# DAC_AFE_Mezzanine.net
KiCad netlist of a schematic drawn in Altium Designer
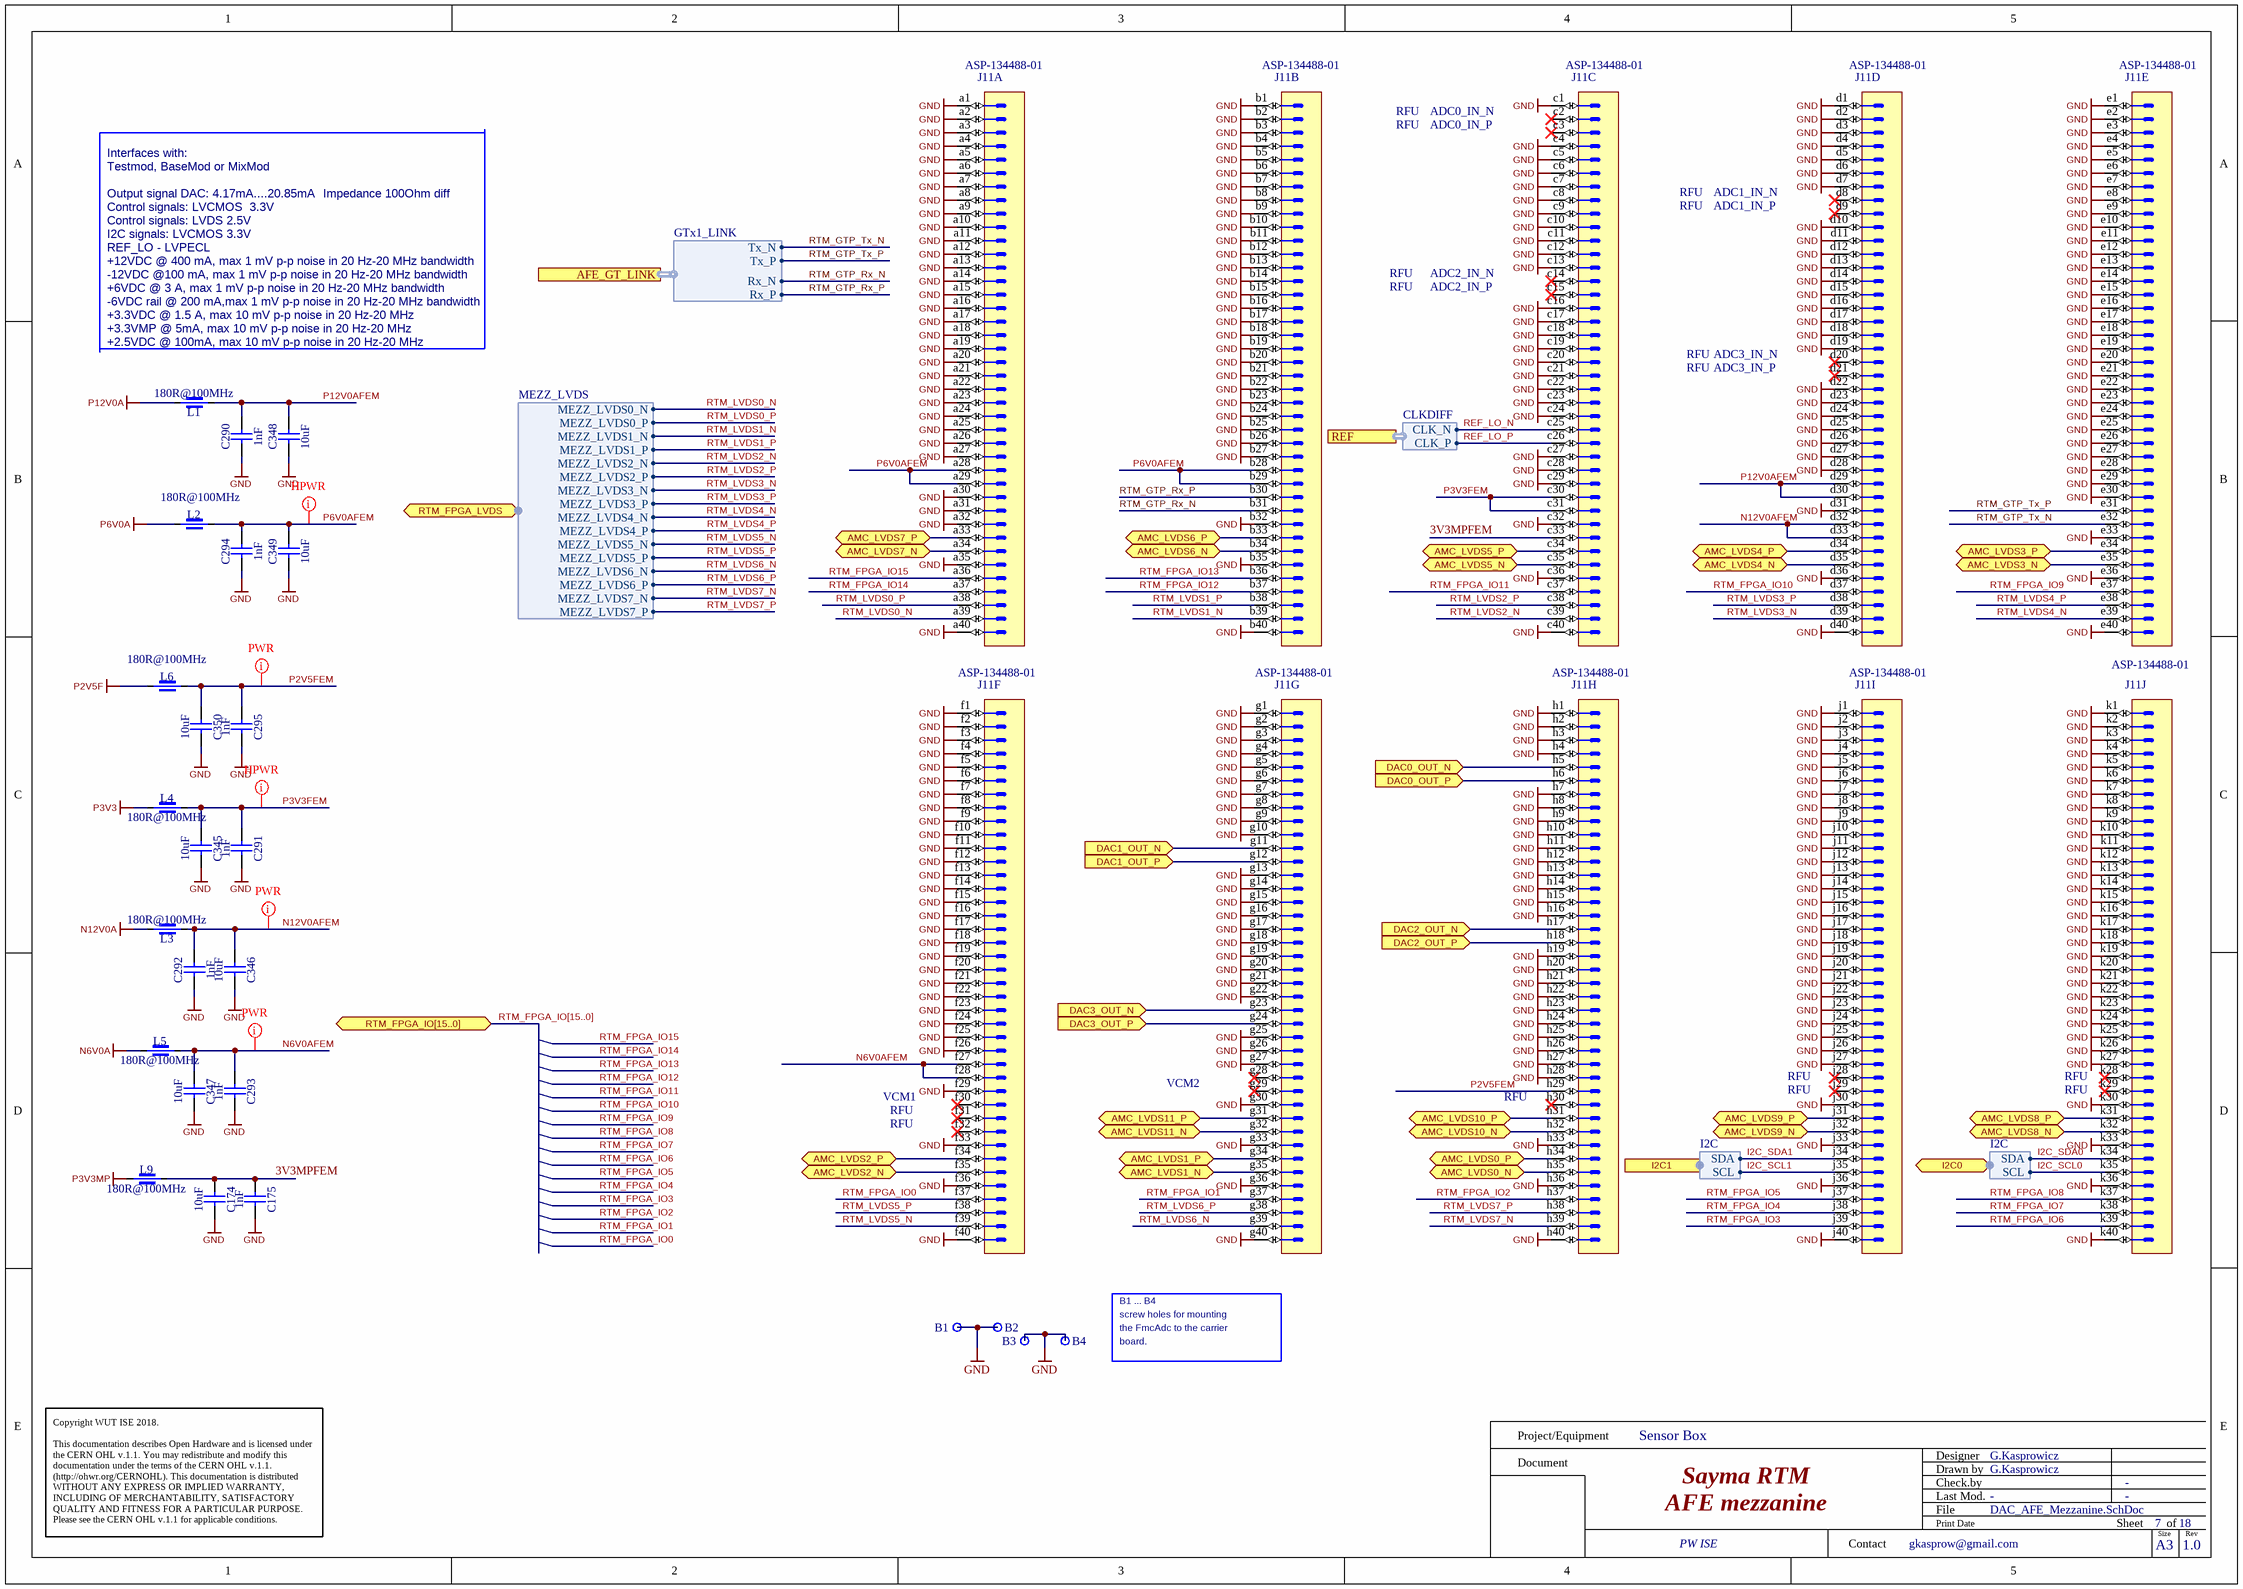
[diagram p0: DAC_AFE_Mezzanine.SchDoc]

(export (version "E")
  (design (tool "Eeschema 10.0.6"))
  (components
    (comp (ref "B1")
      (value "Plated Hole")
      (footprint "MTG270_500")
      (description "Single Terminal Socket")
      (fields (field (name "PART NUMBER") "PLATED_HOLE2.7_PAD5.0") (field (name "AUTHOR") "CERN DEM JMW"))
      (libsource (lib "Eletro-mechanical") (part "Single Terminal Socket"))
    )
    (comp (ref "B2")
      (value "Plated Hole")
      (footprint "MTG270_500")
      (description "Single Terminal Socket")
      (fields (field (name "PART NUMBER") "PLATED_HOLE2.7_PAD5.0") (field (name "AUTHOR") "CERN DEM JMW"))
      (libsource (lib "Eletro-mechanical") (part "Single Terminal Socket"))
    )
    (comp (ref "B3")
      (value "Plated Hole")
      (footprint "MTG270_500")
      (description "Single Terminal Socket")
      (fields (field (name "PART NUMBER") "PLATED_HOLE2.7_PAD5.0") (field (name "AUTHOR") "CERN DEM JMW"))
      (libsource (lib "Eletro-mechanical") (part "Single Terminal Socket"))
    )
    (comp (ref "B4")
      (value "Plated Hole")
      (footprint "MTG270_500")
      (description "Single Terminal Socket")
      (fields (field (name "PART NUMBER") "PLATED_HOLE2.7_PAD5.0") (field (name "AUTHOR") "CERN DEM JMW"))
      (libsource (lib "Eletro-mechanical") (part "Single Terminal Socket"))
    )
    (comp (ref "C174")
      (value "10uF")
      (footprint "CAPC3216X180N")
      (description "Non-polarised capacitor")
      (fields
        (field (name "MANUFACTURER PART NUMBER") "CC1206_10uF_25V_10%_X7R")
        (field (name "MANUFACTURER") "GENERIC")
        (field (name "AUTHOR") "CERN DEM JLC")
      )
      (libsource (lib "Capacitors") (part "Capacitor - non polarized"))
    )
    (comp (ref "C175")
      (value "1nF")
      (footprint "CAPC1608X90N")
      (description "Non-polarised capacitor")
      (fields
        (field (name "MANUFACTURER PART NUMBER") "CC0603_1NF_50V_5%_NP0")
        (field (name "MANUFACTURER") "GENERIC")
        (field (name "AUTHOR") "CERN DEM JLC")
      )
      (libsource (lib "Capacitors") (part "Capacitor - non polarized"))
    )
    (comp (ref "C290")
      (value "1nF")
      (footprint "CAPC1608X90N")
      (description "Non-polarised capacitor")
      (fields
        (field (name "MANUFACTURER PART NUMBER") "CC0603_1NF_50V_5%_NP0")
        (field (name "MANUFACTURER") "GENERIC")
        (field (name "AUTHOR") "CERN DEM JLC")
      )
      (libsource (lib "Capacitors") (part "Capacitor - non polarized"))
    )
    (comp (ref "C291")
      (value "1nF")
      (footprint "CAPC1608X90N")
      (description "Non-polarised capacitor")
      (fields
        (field (name "MANUFACTURER PART NUMBER") "CC0603_1NF_50V_5%_NP0")
        (field (name "MANUFACTURER") "GENERIC")
        (field (name "AUTHOR") "CERN DEM JLC")
      )
      (libsource (lib "Capacitors") (part "Capacitor - non polarized"))
    )
    (comp (ref "C292")
      (value "1nF")
      (footprint "CAPC1608X90N")
      (description "Non-polarised capacitor")
      (fields
        (field (name "MANUFACTURER PART NUMBER") "CC0603_1NF_50V_5%_NP0")
        (field (name "MANUFACTURER") "GENERIC")
        (field (name "AUTHOR") "CERN DEM JLC")
      )
      (libsource (lib "Capacitors") (part "Capacitor - non polarized"))
    )
    (comp (ref "C293")
      (value "1nF")
      (footprint "CAPC1608X90N")
      (description "Non-polarised capacitor")
      (fields
        (field (name "MANUFACTURER PART NUMBER") "CC0603_1NF_50V_5%_NP0")
        (field (name "MANUFACTURER") "GENERIC")
        (field (name "AUTHOR") "CERN DEM JLC")
      )
      (libsource (lib "Capacitors") (part "Capacitor - non polarized"))
    )
    (comp (ref "C294")
      (value "1nF")
      (footprint "CAPC1608X90N")
      (description "Non-polarised capacitor")
      (fields
        (field (name "MANUFACTURER PART NUMBER") "CC0603_1NF_50V_5%_NP0")
        (field (name "MANUFACTURER") "GENERIC")
        (field (name "AUTHOR") "CERN DEM JLC")
      )
      (libsource (lib "Capacitors") (part "Capacitor - non polarized"))
    )
    (comp (ref "C295")
      (value "1nF")
      (footprint "CAPC1608X90N")
      (description "Non-polarised capacitor")
      (fields
        (field (name "MANUFACTURER PART NUMBER") "CC0603_1NF_50V_5%_NP0")
        (field (name "MANUFACTURER") "GENERIC")
        (field (name "AUTHOR") "CERN DEM JLC")
      )
      (libsource (lib "Capacitors") (part "Capacitor - non polarized"))
    )
    (comp (ref "C345")
      (value "10uF")
      (footprint "CAPC3216X180N")
      (description "Non-polarised capacitor")
      (fields
        (field (name "MANUFACTURER PART NUMBER") "CC1206_10uF_25V_10%_X7R")
        (field (name "MANUFACTURER") "GENERIC")
        (field (name "AUTHOR") "CERN DEM JLC")
      )
      (libsource (lib "Capacitors") (part "Capacitor - non polarized"))
    )
    (comp (ref "C346")
      (value "10uF")
      (footprint "CAPC3216X180N")
      (description "Non-polarised capacitor")
      (fields
        (field (name "MANUFACTURER PART NUMBER") "CC1206_10uF_25V_10%_X7R")
        (field (name "MANUFACTURER") "GENERIC")
        (field (name "AUTHOR") "CERN DEM JLC")
      )
      (libsource (lib "Capacitors") (part "Capacitor - non polarized"))
    )
    (comp (ref "C347")
      (value "10uF")
      (footprint "CAPC3216X180N")
      (description "Non-polarised capacitor")
      (fields
        (field (name "MANUFACTURER PART NUMBER") "CC1206_10uF_25V_10%_X7R")
        (field (name "MANUFACTURER") "GENERIC")
        (field (name "AUTHOR") "CERN DEM JLC")
      )
      (libsource (lib "Capacitors") (part "Capacitor - non polarized"))
    )
    (comp (ref "C348")
      (value "10uF")
      (footprint "CAPC3216X180N")
      (description "Non-polarised capacitor")
      (fields
        (field (name "MANUFACTURER PART NUMBER") "CC1206_10uF_25V_10%_X7R")
        (field (name "MANUFACTURER") "GENERIC")
        (field (name "AUTHOR") "CERN DEM JLC")
      )
      (libsource (lib "Capacitors") (part "Capacitor - non polarized"))
    )
    (comp (ref "C349")
      (value "10uF")
      (footprint "CAPC3216X180N")
      (description "Non-polarised capacitor")
      (fields
        (field (name "MANUFACTURER PART NUMBER") "CC1206_10uF_25V_10%_X7R")
        (field (name "MANUFACTURER") "GENERIC")
        (field (name "AUTHOR") "CERN DEM JLC")
      )
      (libsource (lib "Capacitors") (part "Capacitor - non polarized"))
    )
    (comp (ref "C350")
      (value "10uF")
      (footprint "CAPC3216X180N")
      (description "Non-polarised capacitor")
      (fields
        (field (name "MANUFACTURER PART NUMBER") "CC1206_10uF_25V_10%_X7R")
        (field (name "MANUFACTURER") "GENERIC")
        (field (name "AUTHOR") "CERN DEM JLC")
      )
      (libsource (lib "Capacitors") (part "Capacitor - non polarized"))
    )
    (comp (ref "J11")
      (value "VITA 57")
      (footprint "SAMTEC_ASP-134488-01")
      (description "Connector VITA 57, 400 Male contacts in 10 row abcdefghj")
      (fields
        (field (name "MANUFACTURER PART NUMBER") "ASP-134488-01")
        (field (name "MANUFACTURER") "SAMTEC")
        (field (name "PART NUMBER") "SAMTEC_ASP-134488-01")
        (field (name "AUTHOR") "CERN DEM JLC")
      )
      (libsource (lib "Connectors") (part "Connector VITA 57 400 Male (abcdefghjk)"))
    )
    (comp (ref "L1")
      (value "180R@100MHz")
      (footprint "INDC4516X180N")
      (fields
        (field (name "MANUFACTURER PART NUMBER") "BLM41PG181SN1L")
        (field (name "MANUFACTURER") "MURATA")
        (field (name "PART NUMBER") "IND1806_MURATA_BLM41PG181SN1L")
        (field (name "AUTHOR") "CERN DEM JLC")
      )
      (libsource (lib "") (part "Ferrite Bead_3"))
    )
    (comp (ref "L2")
      (value "180R@100MHz")
      (footprint "INDC4516X180N")
      (fields
        (field (name "MANUFACTURER PART NUMBER") "BLM41PG181SN1L")
        (field (name "MANUFACTURER") "MURATA")
        (field (name "PART NUMBER") "IND1806_MURATA_BLM41PG181SN1L")
        (field (name "AUTHOR") "CERN DEM JLC")
      )
      (libsource (lib "") (part "Ferrite Bead_2"))
    )
    (comp (ref "L3")
      (value "180R@100MHz")
      (footprint "INDC4516X180N")
      (fields
        (field (name "MANUFACTURER PART NUMBER") "BLM41PG181SN1L")
        (field (name "MANUFACTURER") "MURATA")
        (field (name "PART NUMBER") "IND1806_MURATA_BLM41PG181SN1L")
        (field (name "AUTHOR") "CERN DEM JLC")
      )
      (libsource (lib "Inductors & Transformers") (part "Ferrite Bead"))
    )
    (comp (ref "L4")
      (value "180R@100MHz")
      (footprint "INDC4516X180N")
      (fields
        (field (name "MANUFACTURER PART NUMBER") "BLM41PG181SN1L")
        (field (name "MANUFACTURER") "MURATA")
        (field (name "PART NUMBER") "IND1806_MURATA_BLM41PG181SN1L")
        (field (name "AUTHOR") "CERN DEM JLC")
      )
      (libsource (lib "") (part "Ferrite Bead_1"))
    )
    (comp (ref "L5")
      (value "180R@100MHz")
      (footprint "INDC4516X180N")
      (fields
        (field (name "MANUFACTURER PART NUMBER") "BLM41PG181SN1L")
        (field (name "MANUFACTURER") "MURATA")
        (field (name "PART NUMBER") "IND1806_MURATA_BLM41PG181SN1L")
        (field (name "AUTHOR") "CERN DEM JLC")
      )
      (libsource (lib "") (part "Ferrite Bead_1"))
    )
    (comp (ref "L6")
      (value "180R@100MHz")
      (footprint "INDC4516X180N")
      (fields
        (field (name "MANUFACTURER PART NUMBER") "BLM41PG181SN1L")
        (field (name "MANUFACTURER") "MURATA")
        (field (name "PART NUMBER") "IND1806_MURATA_BLM41PG181SN1L")
        (field (name "AUTHOR") "CERN DEM JLC")
      )
      (libsource (lib "") (part "Ferrite Bead_1"))
    )
    (comp (ref "L9")
      (value "180R@100MHz")
      (footprint "INDC4516X180N")
      (fields
        (field (name "MANUFACTURER PART NUMBER") "BLM41PG181SN1L")
        (field (name "MANUFACTURER") "MURATA")
        (field (name "PART NUMBER") "IND1806_MURATA_BLM41PG181SN1L")
        (field (name "AUTHOR") "CERN DEM JLC")
      )
      (libsource (lib "") (part "Ferrite Bead_1"))
    )
  )
  (nets
    (net (code "5") (name "/3V3MPFEM") (class "Default")
      (node (ref "C174") (pin "2") (pinfunction "2_2") (pintype "passive"))
      (node (ref "C175") (pin "2") (pinfunction "2_2") (pintype "passive"))
      (node (ref "J11") (pin "c33") (pinfunction "c33_c33") (pintype "bidirectional"))
      (node (ref "L9") (pin "1") (pinfunction "1_1") (pintype "passive"))
    )
    (net (code "6") (name "/AMC_LVDS0_N") (class "Default")
      (node (ref "J11") (pin "h35") (pinfunction "h35_h35") (pintype "bidirectional"))
    )
    (net (code "7") (name "/AMC_LVDS0_P") (class "Default")
      (node (ref "J11") (pin "h34") (pinfunction "h34_h34") (pintype "bidirectional"))
    )
    (net (code "8") (name "/AMC_LVDS1_N") (class "Default")
      (node (ref "J11") (pin "g35") (pinfunction "g35_g35") (pintype "bidirectional"))
    )
    (net (code "9") (name "/AMC_LVDS1_P") (class "Default")
      (node (ref "J11") (pin "g34") (pinfunction "g34_g34") (pintype "bidirectional"))
    )
    (net (code "10") (name "/AMC_LVDS2_N") (class "Default")
      (node (ref "J11") (pin "f35") (pinfunction "f35_f35") (pintype "bidirectional"))
    )
    (net (code "11") (name "/AMC_LVDS2_P") (class "Default")
      (node (ref "J11") (pin "f34") (pinfunction "f34_f34") (pintype "bidirectional"))
    )
    (net (code "12") (name "/AMC_LVDS3_N") (class "Default")
      (node (ref "J11") (pin "e35") (pinfunction "e35_e35") (pintype "bidirectional"))
    )
    (net (code "13") (name "/AMC_LVDS3_P") (class "Default")
      (node (ref "J11") (pin "e34") (pinfunction "e34_e34") (pintype "bidirectional"))
    )
    (net (code "14") (name "/AMC_LVDS4_N") (class "Default")
      (node (ref "J11") (pin "d35") (pinfunction "d35_d35") (pintype "bidirectional"))
    )
    (net (code "15") (name "/AMC_LVDS4_P") (class "Default")
      (node (ref "J11") (pin "d34") (pinfunction "d34_d34") (pintype "bidirectional"))
    )
    (net (code "16") (name "/AMC_LVDS5_N") (class "Default")
      (node (ref "J11") (pin "c35") (pinfunction "c35_c35") (pintype "bidirectional"))
    )
    (net (code "17") (name "/AMC_LVDS5_P") (class "Default")
      (node (ref "J11") (pin "c34") (pinfunction "c34_c34") (pintype "bidirectional"))
    )
    (net (code "18") (name "/AMC_LVDS6_N") (class "Default")
      (node (ref "J11") (pin "b34") (pinfunction "b34_b34") (pintype "bidirectional"))
    )
    (net (code "19") (name "/AMC_LVDS6_P") (class "Default")
      (node (ref "J11") (pin "b33") (pinfunction "b33_b33") (pintype "bidirectional"))
    )
    (net (code "20") (name "/AMC_LVDS7_N") (class "Default")
      (node (ref "J11") (pin "a34") (pinfunction "a34_a34") (pintype "bidirectional"))
    )
    (net (code "21") (name "/AMC_LVDS7_P") (class "Default")
      (node (ref "J11") (pin "a33") (pinfunction "a33_a33") (pintype "bidirectional"))
    )
    (net (code "22") (name "/AMC_LVDS8_N") (class "Default")
      (node (ref "J11") (pin "k32") (pinfunction "k32_k32") (pintype "bidirectional"))
    )
    (net (code "23") (name "/AMC_LVDS8_P") (class "Default")
      (node (ref "J11") (pin "k31") (pinfunction "k31_k31") (pintype "bidirectional"))
    )
    (net (code "24") (name "/AMC_LVDS9_N") (class "Default")
      (node (ref "J11") (pin "j32") (pinfunction "j32_j32") (pintype "bidirectional"))
    )
    (net (code "25") (name "/AMC_LVDS9_P") (class "Default")
      (node (ref "J11") (pin "j31") (pinfunction "j31_j31") (pintype "bidirectional"))
    )
    (net (code "26") (name "/AMC_LVDS10_N") (class "Default")
      (node (ref "J11") (pin "h32") (pinfunction "h32_h32") (pintype "bidirectional"))
    )
    (net (code "27") (name "/AMC_LVDS10_P") (class "Default")
      (node (ref "J11") (pin "h31") (pinfunction "h31_h31") (pintype "bidirectional"))
    )
    (net (code "28") (name "/AMC_LVDS11_N") (class "Default")
      (node (ref "J11") (pin "g32") (pinfunction "g32_g32") (pintype "bidirectional"))
    )
    (net (code "29") (name "/AMC_LVDS11_P") (class "Default")
      (node (ref "J11") (pin "g31") (pinfunction "g31_g31") (pintype "bidirectional"))
    )
    (net (code "30") (name "/DAC0_OUT_N") (class "Default")
      (node (ref "J11") (pin "h5") (pinfunction "h5_h5") (pintype "bidirectional"))
    )
    (net (code "31") (name "/DAC0_OUT_P") (class "Default")
      (node (ref "J11") (pin "h6") (pinfunction "h6_h6") (pintype "bidirectional"))
    )
    (net (code "32") (name "/DAC1_OUT_N") (class "Default")
      (node (ref "J11") (pin "g11") (pinfunction "g11_g11") (pintype "bidirectional"))
    )
    (net (code "33") (name "/DAC1_OUT_P") (class "Default")
      (node (ref "J11") (pin "g12") (pinfunction "g12_g12") (pintype "bidirectional"))
    )
    (net (code "34") (name "/DAC2_OUT_N") (class "Default")
      (node (ref "J11") (pin "h17") (pinfunction "h17_h17") (pintype "bidirectional"))
    )
    (net (code "35") (name "/DAC2_OUT_P") (class "Default")
      (node (ref "J11") (pin "h18") (pinfunction "h18_h18") (pintype "bidirectional"))
    )
    (net (code "36") (name "/DAC3_OUT_N") (class "Default")
      (node (ref "J11") (pin "g23") (pinfunction "g23_g23") (pintype "bidirectional"))
    )
    (net (code "37") (name "/DAC3_OUT_P") (class "Default")
      (node (ref "J11") (pin "g24") (pinfunction "g24_g24") (pintype "bidirectional"))
    )
    (net (code "38") (name "/I2C_SCL0") (class "Default")
      (node (ref "J11") (pin "k35") (pinfunction "k35_k35") (pintype "bidirectional"))
    )
    (net (code "39") (name "/I2C_SCL1") (class "Default")
      (node (ref "J11") (pin "j35") (pinfunction "j35_j35") (pintype "bidirectional"))
    )
    (net (code "40") (name "/I2C_SDA0") (class "Default")
      (node (ref "J11") (pin "k34") (pinfunction "k34_k34") (pintype "bidirectional"))
    )
    (net (code "41") (name "/I2C_SDA1") (class "Default")
      (node (ref "J11") (pin "j34") (pinfunction "j34_j34") (pintype "bidirectional"))
    )
    (net (code "42") (name "/N6V0AFEM") (class "Default")
      (node (ref "C293") (pin "2") (pinfunction "2_2") (pintype "passive"))
      (node (ref "C347") (pin "2") (pinfunction "2_2") (pintype "passive"))
      (node (ref "J11") (pin "f27") (pinfunction "f27_f27") (pintype "bidirectional"))
      (node (ref "J11") (pin "f28") (pinfunction "f28_f28") (pintype "bidirectional"))
      (node (ref "L5") (pin "1") (pinfunction "1_1") (pintype "passive"))
    )
    (net (code "43") (name "/N12V0AFEM") (class "Default")
      (node (ref "C292") (pin "2") (pinfunction "2_2") (pintype "passive"))
      (node (ref "C346") (pin "1") (pinfunction "1_1") (pintype "passive"))
      (node (ref "J11") (pin "d32") (pinfunction "d32_d32") (pintype "bidirectional"))
      (node (ref "J11") (pin "d33") (pinfunction "d33_d33") (pintype "bidirectional"))
      (node (ref "L3") (pin "1") (pinfunction "1_1") (pintype "passive"))
    )
    (net (code "44") (name "/P2V5FEM") (class "Default")
      (node (ref "C295") (pin "2") (pinfunction "2_2") (pintype "passive"))
      (node (ref "C350") (pin "2") (pinfunction "2_2") (pintype "passive"))
      (node (ref "J11") (pin "h29") (pinfunction "h29_h29") (pintype "bidirectional"))
      (node (ref "L6") (pin "1") (pinfunction "1_1") (pintype "passive"))
    )
    (net (code "45") (name "/P3V3FEM") (class "Default")
      (node (ref "C291") (pin "2") (pinfunction "2_2") (pintype "passive"))
      (node (ref "C345") (pin "2") (pinfunction "2_2") (pintype "passive"))
      (node (ref "J11") (pin "c30") (pinfunction "c30_c30") (pintype "bidirectional"))
      (node (ref "J11") (pin "c31") (pinfunction "c31_c31") (pintype "bidirectional"))
      (node (ref "L4") (pin "1") (pinfunction "1_1") (pintype "passive"))
    )
    (net (code "46") (name "/P6V0AFEM") (class "Default")
      (node (ref "C294") (pin "2") (pinfunction "2_2") (pintype "passive"))
      (node (ref "C349") (pin "2") (pinfunction "2_2") (pintype "passive"))
      (node (ref "J11") (pin "a28") (pinfunction "a28_a28") (pintype "bidirectional"))
      (node (ref "J11") (pin "a29") (pinfunction "a29_a29") (pintype "bidirectional"))
      (node (ref "J11") (pin "b28") (pinfunction "b28_b28") (pintype "bidirectional"))
      (node (ref "J11") (pin "b29") (pinfunction "b29_b29") (pintype "bidirectional"))
      (node (ref "L2") (pin "2") (pinfunction "2_2") (pintype "passive"))
    )
    (net (code "47") (name "/P12V0AFEM") (class "Default")
      (node (ref "C290") (pin "1") (pinfunction "1_1") (pintype "passive"))
      (node (ref "C348") (pin "1") (pinfunction "1_1") (pintype "passive"))
      (node (ref "J11") (pin "d29") (pinfunction "d29_d29") (pintype "bidirectional"))
      (node (ref "J11") (pin "d30") (pinfunction "d30_d30") (pintype "bidirectional"))
      (node (ref "L1") (pin "2") (pinfunction "2_2") (pintype "passive"))
    )
    (net (code "48") (name "/REF_LO_N") (class "Default")
      (node (ref "J11") (pin "c25") (pinfunction "c25_c25") (pintype "bidirectional"))
    )
    (net (code "49") (name "/REF_LO_P") (class "Default")
      (node (ref "J11") (pin "c26") (pinfunction "c26_c26") (pintype "bidirectional"))
    )
    (net (code "50") (name "/RTM_FPGA_IO0") (class "Default")
      (node (ref "J11") (pin "f37") (pinfunction "f37_f37") (pintype "bidirectional"))
    )
    (net (code "51") (name "/RTM_FPGA_IO1") (class "Default")
      (node (ref "J11") (pin "g37") (pinfunction "g37_g37") (pintype "bidirectional"))
    )
    (net (code "52") (name "/RTM_FPGA_IO2") (class "Default")
      (node (ref "J11") (pin "h37") (pinfunction "h37_h37") (pintype "bidirectional"))
    )
    (net (code "53") (name "/RTM_FPGA_IO3") (class "Default")
      (node (ref "J11") (pin "j39") (pinfunction "j39_j39") (pintype "bidirectional"))
    )
    (net (code "54") (name "/RTM_FPGA_IO4") (class "Default")
      (node (ref "J11") (pin "j38") (pinfunction "j38_j38") (pintype "bidirectional"))
    )
    (net (code "55") (name "/RTM_FPGA_IO5") (class "Default")
      (node (ref "J11") (pin "j37") (pinfunction "j37_j37") (pintype "bidirectional"))
    )
    (net (code "56") (name "/RTM_FPGA_IO6") (class "Default")
      (node (ref "J11") (pin "k39") (pinfunction "k39_k39") (pintype "bidirectional"))
    )
    (net (code "57") (name "/RTM_FPGA_IO7") (class "Default")
      (node (ref "J11") (pin "k38") (pinfunction "k38_k38") (pintype "bidirectional"))
    )
    (net (code "58") (name "/RTM_FPGA_IO8") (class "Default")
      (node (ref "J11") (pin "k37") (pinfunction "k37_k37") (pintype "bidirectional"))
    )
    (net (code "59") (name "/RTM_FPGA_IO9") (class "Default")
      (node (ref "J11") (pin "e37") (pinfunction "e37_e37") (pintype "bidirectional"))
    )
    (net (code "60") (name "/RTM_FPGA_IO10") (class "Default")
      (node (ref "J11") (pin "d37") (pinfunction "d37_d37") (pintype "bidirectional"))
    )
    (net (code "61") (name "/RTM_FPGA_IO11") (class "Default")
      (node (ref "J11") (pin "c37") (pinfunction "c37_c37") (pintype "bidirectional"))
    )
    (net (code "62") (name "/RTM_FPGA_IO12") (class "Default")
      (node (ref "J11") (pin "b37") (pinfunction "b37_b37") (pintype "bidirectional"))
    )
    (net (code "63") (name "/RTM_FPGA_IO13") (class "Default")
      (node (ref "J11") (pin "b36") (pinfunction "b36_b36") (pintype "bidirectional"))
    )
    (net (code "64") (name "/RTM_FPGA_IO14") (class "Default")
      (node (ref "J11") (pin "a37") (pinfunction "a37_a37") (pintype "bidirectional"))
    )
    (net (code "65") (name "/RTM_FPGA_IO15") (class "Default")
      (node (ref "J11") (pin "a36") (pinfunction "a36_a36") (pintype "bidirectional"))
    )
    (net (code "67") (name "/RTM_GTP_Rx_N") (class "Default")
      (node (ref "J11") (pin "b31") (pinfunction "b31_b31") (pintype "bidirectional"))
    )
    (net (code "68") (name "/RTM_GTP_Rx_P") (class "Default")
      (node (ref "J11") (pin "b30") (pinfunction "b30_b30") (pintype "bidirectional"))
    )
    (net (code "69") (name "/RTM_GTP_Tx_N") (class "Default")
      (node (ref "J11") (pin "e32") (pinfunction "e32_e32") (pintype "bidirectional"))
    )
    (net (code "70") (name "/RTM_GTP_Tx_P") (class "Default")
      (node (ref "J11") (pin "e31") (pinfunction "e31_e31") (pintype "bidirectional"))
    )
    (net (code "71") (name "/RTM_LVDS0_N") (class "Default")
      (node (ref "J11") (pin "a39") (pinfunction "a39_a39") (pintype "bidirectional"))
    )
    (net (code "72") (name "/RTM_LVDS0_P") (class "Default")
      (node (ref "J11") (pin "a38") (pinfunction "a38_a38") (pintype "bidirectional"))
    )
    (net (code "73") (name "/RTM_LVDS1_N") (class "Default")
      (node (ref "J11") (pin "b39") (pinfunction "b39_b39") (pintype "bidirectional"))
    )
    (net (code "74") (name "/RTM_LVDS1_P") (class "Default")
      (node (ref "J11") (pin "b38") (pinfunction "b38_b38") (pintype "bidirectional"))
    )
    (net (code "75") (name "/RTM_LVDS2_N") (class "Default")
      (node (ref "J11") (pin "c39") (pinfunction "c39_c39") (pintype "bidirectional"))
    )
    (net (code "76") (name "/RTM_LVDS2_P") (class "Default")
      (node (ref "J11") (pin "c38") (pinfunction "c38_c38") (pintype "bidirectional"))
    )
    (net (code "77") (name "/RTM_LVDS3_N") (class "Default")
      (node (ref "J11") (pin "d39") (pinfunction "d39_d39") (pintype "bidirectional"))
    )
    (net (code "78") (name "/RTM_LVDS3_P") (class "Default")
      (node (ref "J11") (pin "d38") (pinfunction "d38_d38") (pintype "bidirectional"))
    )
    (net (code "79") (name "/RTM_LVDS4_N") (class "Default")
      (node (ref "J11") (pin "e39") (pinfunction "e39_e39") (pintype "bidirectional"))
    )
    (net (code "80") (name "/RTM_LVDS4_P") (class "Default")
      (node (ref "J11") (pin "e38") (pinfunction "e38_e38") (pintype "bidirectional"))
    )
    (net (code "81") (name "/RTM_LVDS5_N") (class "Default")
      (node (ref "J11") (pin "f39") (pinfunction "f39_f39") (pintype "bidirectional"))
    )
    (net (code "82") (name "/RTM_LVDS5_P") (class "Default")
      (node (ref "J11") (pin "f38") (pinfunction "f38_f38") (pintype "bidirectional"))
    )
    (net (code "83") (name "/RTM_LVDS6_N") (class "Default")
      (node (ref "J11") (pin "g39") (pinfunction "g39_g39") (pintype "bidirectional"))
    )
    (net (code "84") (name "/RTM_LVDS6_P") (class "Default")
      (node (ref "J11") (pin "g38") (pinfunction "g38_g38") (pintype "bidirectional"))
    )
    (net (code "85") (name "/RTM_LVDS7_N") (class "Default")
      (node (ref "J11") (pin "h39") (pinfunction "h39_h39") (pintype "bidirectional"))
    )
    (net (code "86") (name "/RTM_LVDS7_P") (class "Default")
      (node (ref "J11") (pin "h38") (pinfunction "h38_h38") (pintype "bidirectional"))
    )
    (net (code "91") (name "GND") (class "Default")
      (node (ref "B1") (pin "1") (pinfunction "1_1") (pintype "bidirectional"))
      (node (ref "B2") (pin "1") (pinfunction "1_1") (pintype "bidirectional"))
      (node (ref "B3") (pin "1") (pinfunction "1_1") (pintype "bidirectional"))
      (node (ref "B4") (pin "1") (pinfunction "1_1") (pintype "bidirectional"))
      (node (ref "C174") (pin "1") (pinfunction "1_1") (pintype "passive"))
      (node (ref "C175") (pin "1") (pinfunction "1_1") (pintype "passive"))
      (node (ref "C290") (pin "2") (pinfunction "2_2") (pintype "passive"))
      (node (ref "C291") (pin "1") (pinfunction "1_1") (pintype "passive"))
      (node (ref "C292") (pin "1") (pinfunction "1_1") (pintype "passive"))
      (node (ref "C293") (pin "1") (pinfunction "1_1") (pintype "passive"))
      (node (ref "C294") (pin "1") (pinfunction "1_1") (pintype "passive"))
      (node (ref "C295") (pin "1") (pinfunction "1_1") (pintype "passive"))
      (node (ref "C345") (pin "1") (pinfunction "1_1") (pintype "passive"))
      (node (ref "C346") (pin "2") (pinfunction "2_2") (pintype "passive"))
      (node (ref "C347") (pin "1") (pinfunction "1_1") (pintype "passive"))
      (node (ref "C348") (pin "2") (pinfunction "2_2") (pintype "passive"))
      (node (ref "C349") (pin "1") (pinfunction "1_1") (pintype "passive"))
      (node (ref "C350") (pin "1") (pinfunction "1_1") (pintype "passive"))
      (node (ref "J11") (pin "a1") (pinfunction "a1_a1") (pintype "bidirectional"))
      (node (ref "J11") (pin "a10") (pinfunction "a10_a10") (pintype "bidirectional"))
      (node (ref "J11") (pin "a11") (pinfunction "a11_a11") (pintype "bidirectional"))
      (node (ref "J11") (pin "a12") (pinfunction "a12_a12") (pintype "bidirectional"))
      (node (ref "J11") (pin "a13") (pinfunction "a13_a13") (pintype "bidirectional"))
      (node (ref "J11") (pin "a14") (pinfunction "a14_a14") (pintype "bidirectional"))
      (node (ref "J11") (pin "a15") (pinfunction "a15_a15") (pintype "bidirectional"))
      (node (ref "J11") (pin "a16") (pinfunction "a16_a16") (pintype "bidirectional"))
      (node (ref "J11") (pin "a17") (pinfunction "a17_a17") (pintype "bidirectional"))
      (node (ref "J11") (pin "a18") (pinfunction "a18_a18") (pintype "bidirectional"))
      (node (ref "J11") (pin "a19") (pinfunction "a19_a19") (pintype "bidirectional"))
      (node (ref "J11") (pin "a2") (pinfunction "a2_a2") (pintype "bidirectional"))
      (node (ref "J11") (pin "a20") (pinfunction "a20_a20") (pintype "bidirectional"))
      (node (ref "J11") (pin "a21") (pinfunction "a21_a21") (pintype "bidirectional"))
      (node (ref "J11") (pin "a22") (pinfunction "a22_a22") (pintype "bidirectional"))
      (node (ref "J11") (pin "a23") (pinfunction "a23_a23") (pintype "bidirectional"))
      (node (ref "J11") (pin "a24") (pinfunction "a24_a24") (pintype "bidirectional"))
      (node (ref "J11") (pin "a25") (pinfunction "a25_a25") (pintype "bidirectional"))
      (node (ref "J11") (pin "a26") (pinfunction "a26_a26") (pintype "bidirectional"))
      (node (ref "J11") (pin "a27") (pinfunction "a27_a27") (pintype "bidirectional"))
      (node (ref "J11") (pin "a3") (pinfunction "a3_a3") (pintype "bidirectional"))
      (node (ref "J11") (pin "a30") (pinfunction "a30_a30") (pintype "bidirectional"))
      (node (ref "J11") (pin "a31") (pinfunction "a31_a31") (pintype "bidirectional"))
      (node (ref "J11") (pin "a32") (pinfunction "a32_a32") (pintype "bidirectional"))
      (node (ref "J11") (pin "a35") (pinfunction "a35_a35") (pintype "bidirectional"))
      (node (ref "J11") (pin "a4") (pinfunction "a4_a4") (pintype "bidirectional"))
      (node (ref "J11") (pin "a40") (pinfunction "a40_a40") (pintype "bidirectional"))
      (node (ref "J11") (pin "a5") (pinfunction "a5_a5") (pintype "bidirectional"))
      (node (ref "J11") (pin "a6") (pinfunction "a6_a6") (pintype "bidirectional"))
      (node (ref "J11") (pin "a7") (pinfunction "a7_a7") (pintype "bidirectional"))
      (node (ref "J11") (pin "a8") (pinfunction "a8_a8") (pintype "bidirectional"))
      (node (ref "J11") (pin "a9") (pinfunction "a9_a9") (pintype "bidirectional"))
      (node (ref "J11") (pin "b1") (pinfunction "b1_b1") (pintype "bidirectional"))
      (node (ref "J11") (pin "b10") (pinfunction "b10_b10") (pintype "bidirectional"))
      (node (ref "J11") (pin "b11") (pinfunction "b11_b11") (pintype "bidirectional"))
      (node (ref "J11") (pin "b12") (pinfunction "b12_b12") (pintype "bidirectional"))
      (node (ref "J11") (pin "b13") (pinfunction "b13_b13") (pintype "bidirectional"))
      (node (ref "J11") (pin "b14") (pinfunction "b14_b14") (pintype "bidirectional"))
      (node (ref "J11") (pin "b15") (pinfunction "b15_b15") (pintype "bidirectional"))
      (node (ref "J11") (pin "b16") (pinfunction "b16_b16") (pintype "bidirectional"))
      (node (ref "J11") (pin "b17") (pinfunction "b17_b17") (pintype "bidirectional"))
      (node (ref "J11") (pin "b18") (pinfunction "b18_b18") (pintype "bidirectional"))
      (node (ref "J11") (pin "b19") (pinfunction "b19_b19") (pintype "bidirectional"))
      (node (ref "J11") (pin "b2") (pinfunction "b2_b2") (pintype "bidirectional"))
      (node (ref "J11") (pin "b20") (pinfunction "b20_b20") (pintype "bidirectional"))
      (node (ref "J11") (pin "b21") (pinfunction "b21_b21") (pintype "bidirectional"))
      (node (ref "J11") (pin "b22") (pinfunction "b22_b22") (pintype "bidirectional"))
      (node (ref "J11") (pin "b23") (pinfunction "b23_b23") (pintype "bidirectional"))
      (node (ref "J11") (pin "b24") (pinfunction "b24_b24") (pintype "bidirectional"))
      (node (ref "J11") (pin "b25") (pinfunction "b25_b25") (pintype "bidirectional"))
      (node (ref "J11") (pin "b26") (pinfunction "b26_b26") (pintype "bidirectional"))
      (node (ref "J11") (pin "b27") (pinfunction "b27_b27") (pintype "bidirectional"))
      (node (ref "J11") (pin "b3") (pinfunction "b3_b3") (pintype "bidirectional"))
      (node (ref "J11") (pin "b32") (pinfunction "b32_b32") (pintype "bidirectional"))
      (node (ref "J11") (pin "b35") (pinfunction "b35_b35") (pintype "bidirectional"))
      (node (ref "J11") (pin "b4") (pinfunction "b4_b4") (pintype "bidirectional"))
      (node (ref "J11") (pin "b40") (pinfunction "b40_b40") (pintype "bidirectional"))
      (node (ref "J11") (pin "b5") (pinfunction "b5_b5") (pintype "bidirectional"))
      (node (ref "J11") (pin "b6") (pinfunction "b6_b6") (pintype "bidirectional"))
      (node (ref "J11") (pin "b7") (pinfunction "b7_b7") (pintype "bidirectional"))
      (node (ref "J11") (pin "b8") (pinfunction "b8_b8") (pintype "bidirectional"))
      (node (ref "J11") (pin "b9") (pinfunction "b9_b9") (pintype "bidirectional"))
      (node (ref "J11") (pin "c1") (pinfunction "c1_c1") (pintype "bidirectional"))
      (node (ref "J11") (pin "c10") (pinfunction "c10_c10") (pintype "bidirectional"))
      (node (ref "J11") (pin "c11") (pinfunction "c11_c11") (pintype "bidirectional"))
      (node (ref "J11") (pin "c12") (pinfunction "c12_c12") (pintype "bidirectional"))
      (node (ref "J11") (pin "c13") (pinfunction "c13_c13") (pintype "bidirectional"))
      (node (ref "J11") (pin "c16") (pinfunction "c16_c16") (pintype "bidirectional"))
      (node (ref "J11") (pin "c17") (pinfunction "c17_c17") (pintype "bidirectional"))
      (node (ref "J11") (pin "c18") (pinfunction "c18_c18") (pintype "bidirectional"))
      (node (ref "J11") (pin "c19") (pinfunction "c19_c19") (pintype "bidirectional"))
      (node (ref "J11") (pin "c20") (pinfunction "c20_c20") (pintype "bidirectional"))
      (node (ref "J11") (pin "c21") (pinfunction "c21_c21") (pintype "bidirectional"))
      (node (ref "J11") (pin "c22") (pinfunction "c22_c22") (pintype "bidirectional"))
      (node (ref "J11") (pin "c23") (pinfunction "c23_c23") (pintype "bidirectional"))
      (node (ref "J11") (pin "c24") (pinfunction "c24_c24") (pintype "bidirectional"))
      (node (ref "J11") (pin "c27") (pinfunction "c27_c27") (pintype "bidirectional"))
      (node (ref "J11") (pin "c28") (pinfunction "c28_c28") (pintype "bidirectional"))
      (node (ref "J11") (pin "c29") (pinfunction "c29_c29") (pintype "bidirectional"))
      (node (ref "J11") (pin "c32") (pinfunction "c32_c32") (pintype "bidirectional"))
      (node (ref "J11") (pin "c36") (pinfunction "c36_c36") (pintype "bidirectional"))
      (node (ref "J11") (pin "c4") (pinfunction "c4_c4") (pintype "bidirectional"))
      (node (ref "J11") (pin "c40") (pinfunction "c40_c40") (pintype "bidirectional"))
      (node (ref "J11") (pin "c5") (pinfunction "c5_c5") (pintype "bidirectional"))
      (node (ref "J11") (pin "c6") (pinfunction "c6_c6") (pintype "bidirectional"))
      (node (ref "J11") (pin "c7") (pinfunction "c7_c7") (pintype "bidirectional"))
      (node (ref "J11") (pin "c8") (pinfunction "c8_c8") (pintype "bidirectional"))
      (node (ref "J11") (pin "c9") (pinfunction "c9_c9") (pintype "bidirectional"))
      (node (ref "J11") (pin "d1") (pinfunction "d1_d1") (pintype "bidirectional"))
      (node (ref "J11") (pin "d10") (pinfunction "d10_d10") (pintype "bidirectional"))
      (node (ref "J11") (pin "d11") (pinfunction "d11_d11") (pintype "bidirectional"))
      (node (ref "J11") (pin "d12") (pinfunction "d12_d12") (pintype "bidirectional"))
      (node (ref "J11") (pin "d13") (pinfunction "d13_d13") (pintype "bidirectional"))
      (node (ref "J11") (pin "d14") (pinfunction "d14_d14") (pintype "bidirectional"))
      (node (ref "J11") (pin "d15") (pinfunction "d15_d15") (pintype "bidirectional"))
      (node (ref "J11") (pin "d16") (pinfunction "d16_d16") (pintype "bidirectional"))
      (node (ref "J11") (pin "d17") (pinfunction "d17_d17") (pintype "bidirectional"))
      (node (ref "J11") (pin "d18") (pinfunction "d18_d18") (pintype "bidirectional"))
      (node (ref "J11") (pin "d19") (pinfunction "d19_d19") (pintype "bidirectional"))
      (node (ref "J11") (pin "d2") (pinfunction "d2_d2") (pintype "bidirectional"))
      (node (ref "J11") (pin "d22") (pinfunction "d22_d22") (pintype "bidirectional"))
      (node (ref "J11") (pin "d23") (pinfunction "d23_d23") (pintype "bidirectional"))
      (node (ref "J11") (pin "d24") (pinfunction "d24_d24") (pintype "bidirectional"))
      (node (ref "J11") (pin "d25") (pinfunction "d25_d25") (pintype "bidirectional"))
      (node (ref "J11") (pin "d26") (pinfunction "d26_d26") (pintype "bidirectional"))
      (node (ref "J11") (pin "d27") (pinfunction "d27_d27") (pintype "bidirectional"))
      (node (ref "J11") (pin "d28") (pinfunction "d28_d28") (pintype "bidirectional"))
      (node (ref "J11") (pin "d3") (pinfunction "d3_d3") (pintype "bidirectional"))
      (node (ref "J11") (pin "d31") (pinfunction "d31_d31") (pintype "bidirectional"))
      (node (ref "J11") (pin "d36") (pinfunction "d36_d36") (pintype "bidirectional"))
      (node (ref "J11") (pin "d4") (pinfunction "d4_d4") (pintype "bidirectional"))
      (node (ref "J11") (pin "d40") (pinfunction "d40_d40") (pintype "bidirectional"))
      (node (ref "J11") (pin "d5") (pinfunction "d5_d5") (pintype "bidirectional"))
      (node (ref "J11") (pin "d6") (pinfunction "d6_d6") (pintype "bidirectional"))
      (node (ref "J11") (pin "d7") (pinfunction "d7_d7") (pintype "bidirectional"))
      (node (ref "J11") (pin "e1") (pinfunction "e1_e1") (pintype "bidirectional"))
      (node (ref "J11") (pin "e10") (pinfunction "e10_e10") (pintype "bidirectional"))
      (node (ref "J11") (pin "e11") (pinfunction "e11_e11") (pintype "bidirectional"))
      (node (ref "J11") (pin "e12") (pinfunction "e12_e12") (pintype "bidirectional"))
      (node (ref "J11") (pin "e13") (pinfunction "e13_e13") (pintype "bidirectional"))
      (node (ref "J11") (pin "e14") (pinfunction "e14_e14") (pintype "bidirectional"))
      (node (ref "J11") (pin "e15") (pinfunction "e15_e15") (pintype "bidirectional"))
      (node (ref "J11") (pin "e16") (pinfunction "e16_e16") (pintype "bidirectional"))
      (node (ref "J11") (pin "e17") (pinfunction "e17_e17") (pintype "bidirectional"))
      (node (ref "J11") (pin "e18") (pinfunction "e18_e18") (pintype "bidirectional"))
      (node (ref "J11") (pin "e19") (pinfunction "e19_e19") (pintype "bidirectional"))
      (node (ref "J11") (pin "e2") (pinfunction "e2_e2") (pintype "bidirectional"))
      (node (ref "J11") (pin "e20") (pinfunction "e20_e20") (pintype "bidirectional"))
      (node (ref "J11") (pin "e21") (pinfunction "e21_e21") (pintype "bidirectional"))
      (node (ref "J11") (pin "e22") (pinfunction "e22_e22") (pintype "bidirectional"))
      (node (ref "J11") (pin "e23") (pinfunction "e23_e23") (pintype "bidirectional"))
      (node (ref "J11") (pin "e24") (pinfunction "e24_e24") (pintype "bidirectional"))
      (node (ref "J11") (pin "e25") (pinfunction "e25_e25") (pintype "bidirectional"))
      (node (ref "J11") (pin "e26") (pinfunction "e26_e26") (pintype "bidirectional"))
      (node (ref "J11") (pin "e27") (pinfunction "e27_e27") (pintype "bidirectional"))
      (node (ref "J11") (pin "e28") (pinfunction "e28_e28") (pintype "bidirectional"))
      (node (ref "J11") (pin "e29") (pinfunction "e29_e29") (pintype "bidirectional"))
      (node (ref "J11") (pin "e3") (pinfunction "e3_e3") (pintype "bidirectional"))
      (node (ref "J11") (pin "e30") (pinfunction "e30_e30") (pintype "bidirectional"))
      (node (ref "J11") (pin "e33") (pinfunction "e33_e33") (pintype "bidirectional"))
      (node (ref "J11") (pin "e36") (pinfunction "e36_e36") (pintype "bidirectional"))
      (node (ref "J11") (pin "e4") (pinfunction "e4_e4") (pintype "bidirectional"))
      (node (ref "J11") (pin "e40") (pinfunction "e40_e40") (pintype "bidirectional"))
      (node (ref "J11") (pin "e5") (pinfunction "e5_e5") (pintype "bidirectional"))
      (node (ref "J11") (pin "e6") (pinfunction "e6_e6") (pintype "bidirectional"))
      (node (ref "J11") (pin "e7") (pinfunction "e7_e7") (pintype "bidirectional"))
      (node (ref "J11") (pin "e8") (pinfunction "e8_e8") (pintype "bidirectional"))
      (node (ref "J11") (pin "e9") (pinfunction "e9_e9") (pintype "bidirectional"))
      (node (ref "J11") (pin "f1") (pinfunction "f1_f1") (pintype "bidirectional"))
      (node (ref "J11") (pin "f10") (pinfunction "f10_f10") (pintype "bidirectional"))
      (node (ref "J11") (pin "f11") (pinfunction "f11_f11") (pintype "bidirectional"))
      (node (ref "J11") (pin "f12") (pinfunction "f12_f12") (pintype "bidirectional"))
      (node (ref "J11") (pin "f13") (pinfunction "f13_f13") (pintype "bidirectional"))
      (node (ref "J11") (pin "f14") (pinfunction "f14_f14") (pintype "bidirectional"))
      (node (ref "J11") (pin "f15") (pinfunction "f15_f15") (pintype "bidirectional"))
      (node (ref "J11") (pin "f16") (pinfunction "f16_f16") (pintype "bidirectional"))
      (node (ref "J11") (pin "f17") (pinfunction "f17_f17") (pintype "bidirectional"))
      (node (ref "J11") (pin "f18") (pinfunction "f18_f18") (pintype "bidirectional"))
      (node (ref "J11") (pin "f19") (pinfunction "f19_f19") (pintype "bidirectional"))
      (node (ref "J11") (pin "f2") (pinfunction "f2_f2") (pintype "bidirectional"))
      (node (ref "J11") (pin "f20") (pinfunction "f20_f20") (pintype "bidirectional"))
      (node (ref "J11") (pin "f21") (pinfunction "f21_f21") (pintype "bidirectional"))
      (node (ref "J11") (pin "f22") (pinfunction "f22_f22") (pintype "bidirectional"))
      (node (ref "J11") (pin "f23") (pinfunction "f23_f23") (pintype "bidirectional"))
      (node (ref "J11") (pin "f24") (pinfunction "f24_f24") (pintype "bidirectional"))
      (node (ref "J11") (pin "f25") (pinfunction "f25_f25") (pintype "bidirectional"))
      (node (ref "J11") (pin "f26") (pinfunction "f26_f26") (pintype "bidirectional"))
      (node (ref "J11") (pin "f29") (pinfunction "f29_f29") (pintype "bidirectional"))
      (node (ref "J11") (pin "f3") (pinfunction "f3_f3") (pintype "bidirectional"))
      (node (ref "J11") (pin "f33") (pinfunction "f33_f33") (pintype "bidirectional"))
      (node (ref "J11") (pin "f36") (pinfunction "f36_f36") (pintype "bidirectional"))
      (node (ref "J11") (pin "f4") (pinfunction "f4_f4") (pintype "bidirectional"))
      (node (ref "J11") (pin "f40") (pinfunction "f40_f40") (pintype "bidirectional"))
      (node (ref "J11") (pin "f5") (pinfunction "f5_f5") (pintype "bidirectional"))
      (node (ref "J11") (pin "f6") (pinfunction "f6_f6") (pintype "bidirectional"))
      (node (ref "J11") (pin "f7") (pinfunction "f7_f7") (pintype "bidirectional"))
      (node (ref "J11") (pin "f8") (pinfunction "f8_f8") (pintype "bidirectional"))
      (node (ref "J11") (pin "f9") (pinfunction "f9_f9") (pintype "bidirectional"))
      (node (ref "J11") (pin "g1") (pinfunction "g1_g1") (pintype "bidirectional"))
      (node (ref "J11") (pin "g10") (pinfunction "g10_g10") (pintype "bidirectional"))
      (node (ref "J11") (pin "g13") (pinfunction "g13_g13") (pintype "bidirectional"))
      (node (ref "J11") (pin "g14") (pinfunction "g14_g14") (pintype "bidirectional"))
      (node (ref "J11") (pin "g15") (pinfunction "g15_g15") (pintype "bidirectional"))
      (node (ref "J11") (pin "g16") (pinfunction "g16_g16") (pintype "bidirectional"))
      (node (ref "J11") (pin "g17") (pinfunction "g17_g17") (pintype "bidirectional"))
      (node (ref "J11") (pin "g18") (pinfunction "g18_g18") (pintype "bidirectional"))
      (node (ref "J11") (pin "g19") (pinfunction "g19_g19") (pintype "bidirectional"))
      (node (ref "J11") (pin "g2") (pinfunction "g2_g2") (pintype "bidirectional"))
      (node (ref "J11") (pin "g20") (pinfunction "g20_g20") (pintype "bidirectional"))
      (node (ref "J11") (pin "g21") (pinfunction "g21_g21") (pintype "bidirectional"))
      (node (ref "J11") (pin "g22") (pinfunction "g22_g22") (pintype "bidirectional"))
      (node (ref "J11") (pin "g25") (pinfunction "g25_g25") (pintype "bidirectional"))
      (node (ref "J11") (pin "g26") (pinfunction "g26_g26") (pintype "bidirectional"))
      (node (ref "J11") (pin "g27") (pinfunction "g27_g27") (pintype "bidirectional"))
      (node (ref "J11") (pin "g3") (pinfunction "g3_g3") (pintype "bidirectional"))
      (node (ref "J11") (pin "g30") (pinfunction "g30_g30") (pintype "bidirectional"))
      (node (ref "J11") (pin "g33") (pinfunction "g33_g33") (pintype "bidirectional"))
      (node (ref "J11") (pin "g36") (pinfunction "g36_g36") (pintype "bidirectional"))
      (node (ref "J11") (pin "g4") (pinfunction "g4_g4") (pintype "bidirectional"))
      (node (ref "J11") (pin "g40") (pinfunction "g40_g40") (pintype "bidirectional"))
      (node (ref "J11") (pin "g5") (pinfunction "g5_g5") (pintype "bidirectional"))
      (node (ref "J11") (pin "g6") (pinfunction "g6_g6") (pintype "bidirectional"))
      (node (ref "J11") (pin "g7") (pinfunction "g7_g7") (pintype "bidirectional"))
      (node (ref "J11") (pin "g8") (pinfunction "g8_g8") (pintype "bidirectional"))
      (node (ref "J11") (pin "g9") (pinfunction "g9_g9") (pintype "bidirectional"))
      (node (ref "J11") (pin "h1") (pinfunction "h1_h1") (pintype "bidirectional"))
      (node (ref "J11") (pin "h10") (pinfunction "h10_h10") (pintype "bidirectional"))
      (node (ref "J11") (pin "h11") (pinfunction "h11_h11") (pintype "bidirectional"))
      (node (ref "J11") (pin "h12") (pinfunction "h12_h12") (pintype "bidirectional"))
      (node (ref "J11") (pin "h13") (pinfunction "h13_h13") (pintype "bidirectional"))
      (node (ref "J11") (pin "h14") (pinfunction "h14_h14") (pintype "bidirectional"))
      (node (ref "J11") (pin "h15") (pinfunction "h15_h15") (pintype "bidirectional"))
      (node (ref "J11") (pin "h16") (pinfunction "h16_h16") (pintype "bidirectional"))
      (node (ref "J11") (pin "h19") (pinfunction "h19_h19") (pintype "bidirectional"))
      (node (ref "J11") (pin "h2") (pinfunction "h2_h2") (pintype "bidirectional"))
      (node (ref "J11") (pin "h20") (pinfunction "h20_h20") (pintype "bidirectional"))
      (node (ref "J11") (pin "h21") (pinfunction "h21_h21") (pintype "bidirectional"))
      (node (ref "J11") (pin "h22") (pinfunction "h22_h22") (pintype "bidirectional"))
      (node (ref "J11") (pin "h23") (pinfunction "h23_h23") (pintype "bidirectional"))
      (node (ref "J11") (pin "h24") (pinfunction "h24_h24") (pintype "bidirectional"))
      (node (ref "J11") (pin "h25") (pinfunction "h25_h25") (pintype "bidirectional"))
      (node (ref "J11") (pin "h26") (pinfunction "h26_h26") (pintype "bidirectional"))
      (node (ref "J11") (pin "h27") (pinfunction "h27_h27") (pintype "bidirectional"))
      (node (ref "J11") (pin "h28") (pinfunction "h28_h28") (pintype "bidirectional"))
      (node (ref "J11") (pin "h3") (pinfunction "h3_h3") (pintype "bidirectional"))
      (node (ref "J11") (pin "h33") (pinfunction "h33_h33") (pintype "bidirectional"))
      (node (ref "J11") (pin "h36") (pinfunction "h36_h36") (pintype "bidirectional"))
      (node (ref "J11") (pin "h4") (pinfunction "h4_h4") (pintype "bidirectional"))
      (node (ref "J11") (pin "h40") (pinfunction "h40_h40") (pintype "bidirectional"))
      (node (ref "J11") (pin "h7") (pinfunction "h7_h7") (pintype "bidirectional"))
      (node (ref "J11") (pin "h8") (pinfunction "h8_h8") (pintype "bidirectional"))
      (node (ref "J11") (pin "h9") (pinfunction "h9_h9") (pintype "bidirectional"))
      (node (ref "J11") (pin "j1") (pinfunction "j1_j1") (pintype "bidirectional"))
      (node (ref "J11") (pin "j10") (pinfunction "j10_j10") (pintype "bidirectional"))
      (node (ref "J11") (pin "j11") (pinfunction "j11_j11") (pintype "bidirectional"))
      (node (ref "J11") (pin "j12") (pinfunction "j12_j12") (pintype "bidirectional"))
      (node (ref "J11") (pin "j13") (pinfunction "j13_j13") (pintype "bidirectional"))
      (node (ref "J11") (pin "j14") (pinfunction "j14_j14") (pintype "bidirectional"))
      (node (ref "J11") (pin "j15") (pinfunction "j15_j15") (pintype "bidirectional"))
      (node (ref "J11") (pin "j16") (pinfunction "j16_j16") (pintype "bidirectional"))
      (node (ref "J11") (pin "j17") (pinfunction "j17_j17") (pintype "bidirectional"))
      (node (ref "J11") (pin "j18") (pinfunction "j18_j18") (pintype "bidirectional"))
      (node (ref "J11") (pin "j19") (pinfunction "j19_j19") (pintype "bidirectional"))
      (node (ref "J11") (pin "j2") (pinfunction "j2_j2") (pintype "bidirectional"))
      (node (ref "J11") (pin "j20") (pinfunction "j20_j20") (pintype "bidirectional"))
      (node (ref "J11") (pin "j21") (pinfunction "j21_j21") (pintype "bidirectional"))
      (node (ref "J11") (pin "j22") (pinfunction "j22_j22") (pintype "bidirectional"))
      (node (ref "J11") (pin "j23") (pinfunction "j23_j23") (pintype "bidirectional"))
      (node (ref "J11") (pin "j24") (pinfunction "j24_j24") (pintype "bidirectional"))
      (node (ref "J11") (pin "j25") (pinfunction "j25_j25") (pintype "bidirectional"))
      (node (ref "J11") (pin "j26") (pinfunction "j26_j26") (pintype "bidirectional"))
      (node (ref "J11") (pin "j27") (pinfunction "j27_j27") (pintype "bidirectional"))
      (node (ref "J11") (pin "j3") (pinfunction "j3_j3") (pintype "bidirectional"))
      (node (ref "J11") (pin "j30") (pinfunction "j30_j30") (pintype "bidirectional"))
      (node (ref "J11") (pin "j33") (pinfunction "j33_j33") (pintype "bidirectional"))
      (node (ref "J11") (pin "j36") (pinfunction "j36_j36") (pintype "bidirectional"))
      (node (ref "J11") (pin "j4") (pinfunction "j4_j4") (pintype "bidirectional"))
      (node (ref "J11") (pin "j40") (pinfunction "j40_j40") (pintype "bidirectional"))
      (node (ref "J11") (pin "j5") (pinfunction "j5_j5") (pintype "bidirectional"))
      (node (ref "J11") (pin "j6") (pinfunction "j6_j6") (pintype "bidirectional"))
      (node (ref "J11") (pin "j7") (pinfunction "j7_j7") (pintype "bidirectional"))
      (node (ref "J11") (pin "j8") (pinfunction "j8_j8") (pintype "bidirectional"))
      (node (ref "J11") (pin "j9") (pinfunction "j9_j9") (pintype "bidirectional"))
      (node (ref "J11") (pin "k1") (pinfunction "k1_k1") (pintype "bidirectional"))
      (node (ref "J11") (pin "k10") (pinfunction "k10_k10") (pintype "bidirectional"))
      (node (ref "J11") (pin "k11") (pinfunction "k11_k11") (pintype "bidirectional"))
      (node (ref "J11") (pin "k12") (pinfunction "k12_k12") (pintype "bidirectional"))
      (node (ref "J11") (pin "k13") (pinfunction "k13_k13") (pintype "bidirectional"))
      (node (ref "J11") (pin "k14") (pinfunction "k14_k14") (pintype "bidirectional"))
      (node (ref "J11") (pin "k15") (pinfunction "k15_k15") (pintype "bidirectional"))
      (node (ref "J11") (pin "k16") (pinfunction "k16_k16") (pintype "bidirectional"))
      (node (ref "J11") (pin "k17") (pinfunction "k17_k17") (pintype "bidirectional"))
      (node (ref "J11") (pin "k18") (pinfunction "k18_k18") (pintype "bidirectional"))
      (node (ref "J11") (pin "k19") (pinfunction "k19_k19") (pintype "bidirectional"))
      (node (ref "J11") (pin "k2") (pinfunction "k2_k2") (pintype "bidirectional"))
      (node (ref "J11") (pin "k20") (pinfunction "k20_k20") (pintype "bidirectional"))
      (node (ref "J11") (pin "k21") (pinfunction "k21_k21") (pintype "bidirectional"))
      (node (ref "J11") (pin "k22") (pinfunction "k22_k22") (pintype "bidirectional"))
      (node (ref "J11") (pin "k23") (pinfunction "k23_k23") (pintype "bidirectional"))
      (node (ref "J11") (pin "k24") (pinfunction "k24_k24") (pintype "bidirectional"))
      (node (ref "J11") (pin "k25") (pinfunction "k25_k25") (pintype "bidirectional"))
      (node (ref "J11") (pin "k26") (pinfunction "k26_k26") (pintype "bidirectional"))
      (node (ref "J11") (pin "k27") (pinfunction "k27_k27") (pintype "bidirectional"))
      (node (ref "J11") (pin "k3") (pinfunction "k3_k3") (pintype "bidirectional"))
      (node (ref "J11") (pin "k30") (pinfunction "k30_k30") (pintype "bidirectional"))
      (node (ref "J11") (pin "k33") (pinfunction "k33_k33") (pintype "bidirectional"))
      (node (ref "J11") (pin "k36") (pinfunction "k36_k36") (pintype "bidirectional"))
      (node (ref "J11") (pin "k4") (pinfunction "k4_k4") (pintype "bidirectional"))
      (node (ref "J11") (pin "k40") (pinfunction "k40_k40") (pintype "bidirectional"))
      (node (ref "J11") (pin "k5") (pinfunction "k5_k5") (pintype "bidirectional"))
      (node (ref "J11") (pin "k6") (pinfunction "k6_k6") (pintype "bidirectional"))
      (node (ref "J11") (pin "k7") (pinfunction "k7_k7") (pintype "bidirectional"))
      (node (ref "J11") (pin "k8") (pinfunction "k8_k8") (pintype "bidirectional"))
      (node (ref "J11") (pin "k9") (pinfunction "k9_k9") (pintype "bidirectional"))
    )
    (net (code "92") (name "N6V0A") (class "Default")
      (node (ref "L5") (pin "2") (pinfunction "2_2") (pintype "passive"))
    )
    (net (code "93") (name "N12V0A") (class "Default")
      (node (ref "L3") (pin "2") (pinfunction "2_2") (pintype "passive"))
    )
    (net (code "94") (name "P2V5F") (class "Default")
      (node (ref "L6") (pin "2") (pinfunction "2_2") (pintype "passive"))
    )
    (net (code "95") (name "P3V3") (class "Default")
      (node (ref "L4") (pin "2") (pinfunction "2_2") (pintype "passive"))
    )
    (net (code "96") (name "P3V3MP") (class "Default")
      (node (ref "L9") (pin "2") (pinfunction "2_2") (pintype "passive"))
    )
    (net (code "97") (name "P6V0A") (class "Default")
      (node (ref "L2") (pin "1") (pinfunction "1_1") (pintype "passive"))
    )
    (net (code "98") (name "P12V0A") (class "Default")
      (node (ref "L1") (pin "1") (pinfunction "1_1") (pintype "passive"))
    )
    (net (code "99") (name "unconnected-(J11-Padc2)") (class "Default")
      (node (ref "J11") (pin "c2") (pinfunction "c2_c2") (pintype "bidirectional+no_connect"))
    )
    (net (code "100") (name "unconnected-(J11-Padc3)") (class "Default")
      (node (ref "J11") (pin "c3") (pinfunction "c3_c3") (pintype "bidirectional+no_connect"))
    )
    (net (code "101") (name "unconnected-(J11-Padc14)") (class "Default")
      (node (ref "J11") (pin "c14") (pinfunction "c14_c14") (pintype "bidirectional+no_connect"))
    )
    (net (code "102") (name "unconnected-(J11-Padc15)") (class "Default")
      (node (ref "J11") (pin "c15") (pinfunction "c15_c15") (pintype "bidirectional+no_connect"))
    )
    (net (code "103") (name "unconnected-(J11-Padd8)") (class "Default")
      (node (ref "J11") (pin "d8") (pinfunction "d8_d8") (pintype "bidirectional+no_connect"))
    )
    (net (code "104") (name "unconnected-(J11-Padd9)") (class "Default")
      (node (ref "J11") (pin "d9") (pinfunction "d9_d9") (pintype "bidirectional+no_connect"))
    )
    (net (code "105") (name "unconnected-(J11-Padd20)") (class "Default")
      (node (ref "J11") (pin "d20") (pinfunction "d20_d20") (pintype "bidirectional+no_connect"))
    )
    (net (code "106") (name "unconnected-(J11-Padd21)") (class "Default")
      (node (ref "J11") (pin "d21") (pinfunction "d21_d21") (pintype "bidirectional+no_connect"))
    )
    (net (code "107") (name "unconnected-(J11-Padf30)") (class "Default")
      (node (ref "J11") (pin "f30") (pinfunction "f30_f30") (pintype "bidirectional+no_connect"))
    )
    (net (code "108") (name "unconnected-(J11-Padf31)") (class "Default")
      (node (ref "J11") (pin "f31") (pinfunction "f31_f31") (pintype "bidirectional+no_connect"))
    )
    (net (code "109") (name "unconnected-(J11-Padf32)") (class "Default")
      (node (ref "J11") (pin "f32") (pinfunction "f32_f32") (pintype "bidirectional+no_connect"))
    )
    (net (code "110") (name "unconnected-(J11-Padg28)") (class "Default")
      (node (ref "J11") (pin "g28") (pinfunction "g28_g28") (pintype "bidirectional+no_connect"))
    )
    (net (code "111") (name "unconnected-(J11-Padg29)") (class "Default")
      (node (ref "J11") (pin "g29") (pinfunction "g29_g29") (pintype "bidirectional+no_connect"))
    )
    (net (code "112") (name "unconnected-(J11-Padh30)") (class "Default")
      (node (ref "J11") (pin "h30") (pinfunction "h30_h30") (pintype "bidirectional+no_connect"))
    )
    (net (code "113") (name "unconnected-(J11-Padj28)") (class "Default")
      (node (ref "J11") (pin "j28") (pinfunction "j28_j28") (pintype "bidirectional+no_connect"))
    )
    (net (code "114") (name "unconnected-(J11-Padj29)") (class "Default")
      (node (ref "J11") (pin "j29") (pinfunction "j29_j29") (pintype "bidirectional+no_connect"))
    )
    (net (code "115") (name "unconnected-(J11-Padk28)") (class "Default")
      (node (ref "J11") (pin "k28") (pinfunction "k28_k28") (pintype "bidirectional+no_connect"))
    )
    (net (code "116") (name "unconnected-(J11-Padk29)") (class "Default")
      (node (ref "J11") (pin "k29") (pinfunction "k29_k29") (pintype "bidirectional+no_connect"))
    )
  )
)
